# DP_eDP_Adapter_v1_1.net
KiCad netlist of a schematic drawn in EAGLE
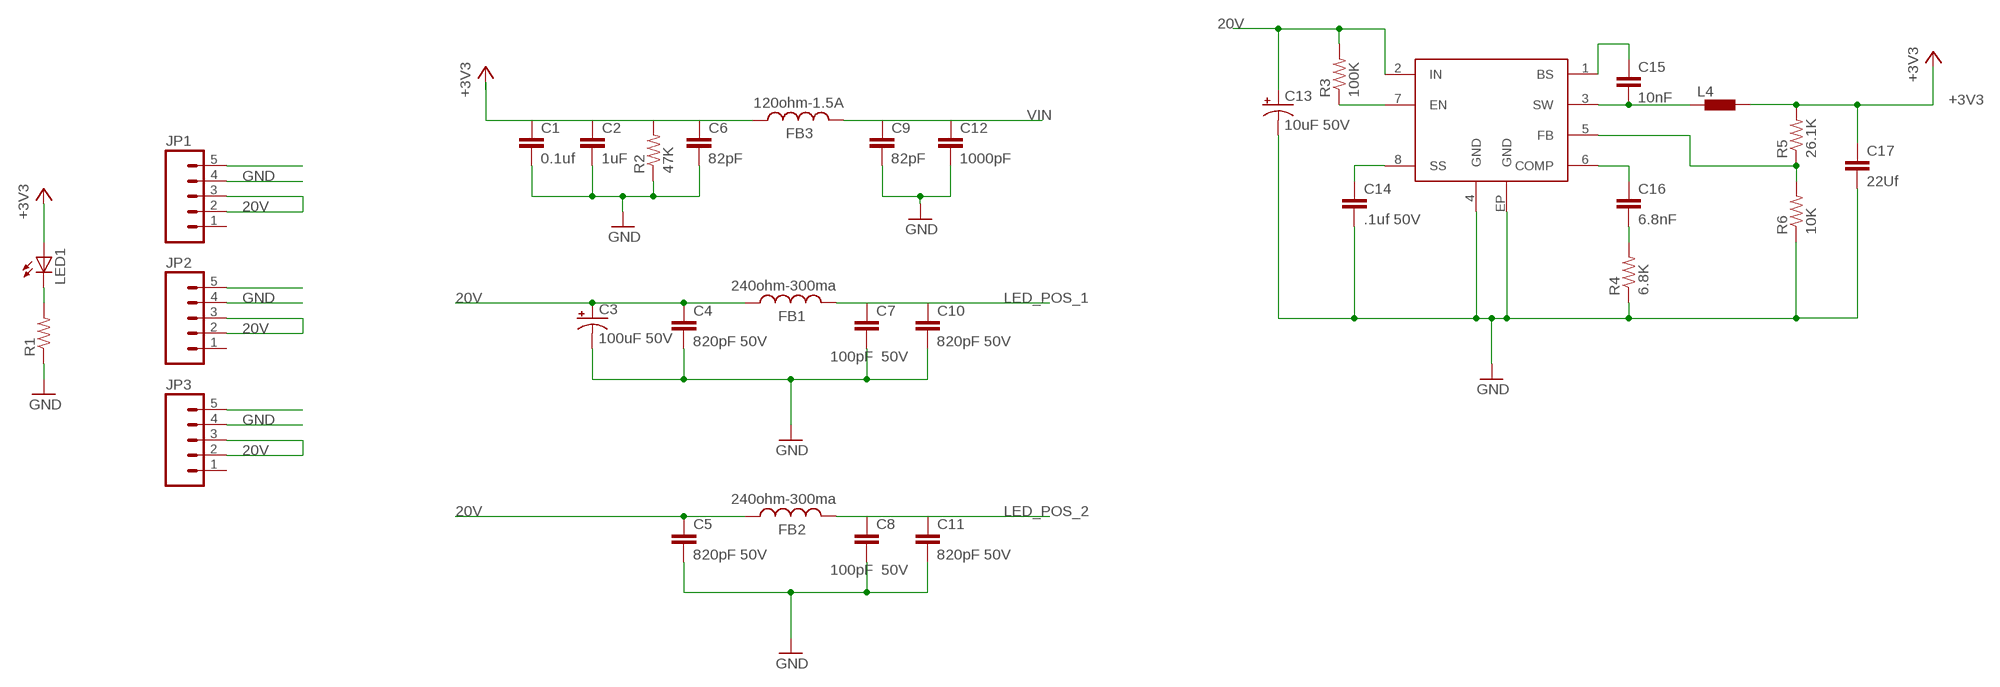
[diagram p0: schematic, sheet 1]
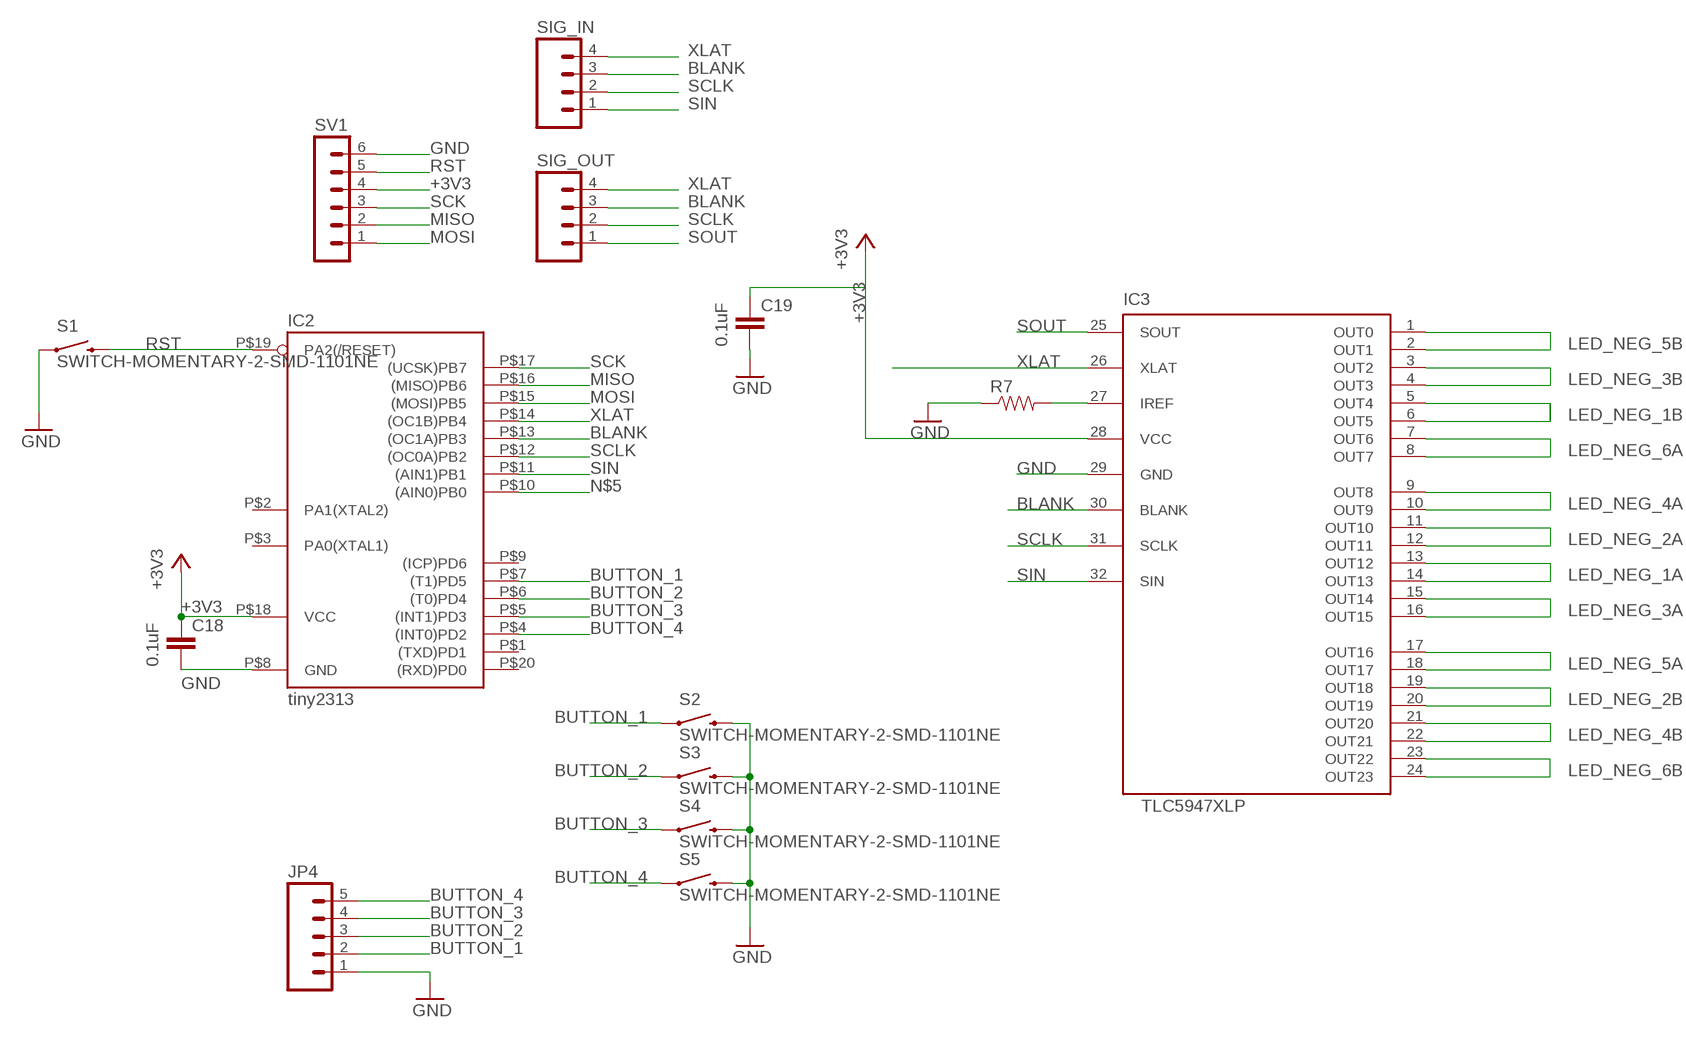
[diagram p1: schematic, sheet 2]
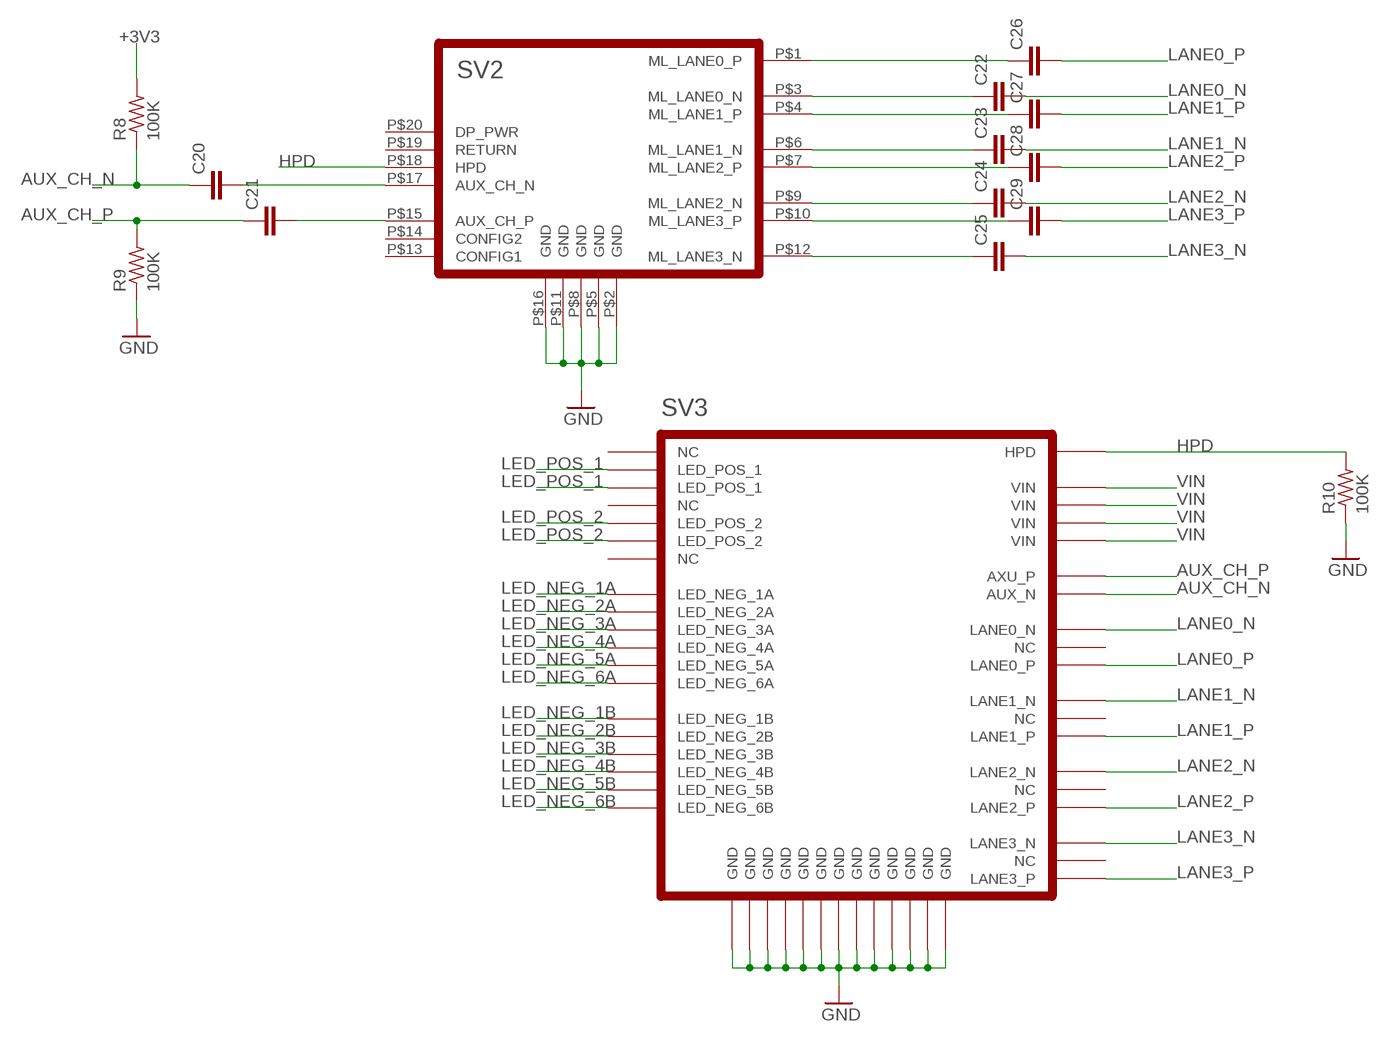
[diagram p2: schematic, sheet 3]

(export (version "E")
  (design (tool "Eeschema 10.0.6"))
  (components
    (comp (ref "C20")
      (value "SPARKFUN-PASSIVES_CAP0402-CAP")
      (footprint "eagle-import:SPARKFUN-PASSIVES_0402-CAP")
      (libsource (lib "eagle-import") (part "SPARKFUN-PASSIVES_CAP0402-CAP"))
    )
    (comp (ref "C21")
      (value "SPARKFUN-PASSIVES_CAP0402-CAP")
      (footprint "eagle-import:SPARKFUN-PASSIVES_0402-CAP")
      (libsource (lib "eagle-import") (part "SPARKFUN-PASSIVES_CAP0402-CAP"))
    )
    (comp (ref "C22")
      (value "SPARKFUN-PASSIVES_CAP0402-CAP")
      (footprint "eagle-import:SPARKFUN-PASSIVES_0402-CAP")
      (libsource (lib "eagle-import") (part "SPARKFUN-PASSIVES_CAP0402-CAP"))
    )
    (comp (ref "C23")
      (value "SPARKFUN-PASSIVES_CAP0402-CAP")
      (footprint "eagle-import:SPARKFUN-PASSIVES_0402-CAP")
      (libsource (lib "eagle-import") (part "SPARKFUN-PASSIVES_CAP0402-CAP"))
    )
    (comp (ref "C24")
      (value "SPARKFUN-PASSIVES_CAP0402-CAP")
      (footprint "eagle-import:SPARKFUN-PASSIVES_0402-CAP")
      (libsource (lib "eagle-import") (part "SPARKFUN-PASSIVES_CAP0402-CAP"))
    )
    (comp (ref "C25")
      (value "SPARKFUN-PASSIVES_CAP0402-CAP")
      (footprint "eagle-import:SPARKFUN-PASSIVES_0402-CAP")
      (libsource (lib "eagle-import") (part "SPARKFUN-PASSIVES_CAP0402-CAP"))
    )
    (comp (ref "C26")
      (value "SPARKFUN-PASSIVES_CAP0402-CAP")
      (footprint "eagle-import:SPARKFUN-PASSIVES_0402-CAP")
      (libsource (lib "eagle-import") (part "SPARKFUN-PASSIVES_CAP0402-CAP"))
    )
    (comp (ref "C27")
      (value "SPARKFUN-PASSIVES_CAP0402-CAP")
      (footprint "eagle-import:SPARKFUN-PASSIVES_0402-CAP")
      (libsource (lib "eagle-import") (part "SPARKFUN-PASSIVES_CAP0402-CAP"))
    )
    (comp (ref "C28")
      (value "SPARKFUN-PASSIVES_CAP0402-CAP")
      (footprint "eagle-import:SPARKFUN-PASSIVES_0402-CAP")
      (libsource (lib "eagle-import") (part "SPARKFUN-PASSIVES_CAP0402-CAP"))
    )
    (comp (ref "C29")
      (value "SPARKFUN-PASSIVES_CAP0402-CAP")
      (footprint "eagle-import:SPARKFUN-PASSIVES_0402-CAP")
      (libsource (lib "eagle-import") (part "SPARKFUN-PASSIVES_CAP0402-CAP"))
    )
    (comp (ref "R8")
      (value "100K")
      (footprint "eagle-import:R0402")
      (libsource (lib "eagle-import") (part "R-US_R0402"))
    )
    (comp (ref "R9")
      (value "100K")
      (footprint "eagle-import:R0402")
      (libsource (lib "eagle-import") (part "R-US_R0402"))
    )
    (comp (ref "R10")
      (value "100K")
      (footprint "eagle-import:R0402")
      (libsource (lib "eagle-import") (part "R-US_R0402"))
    )
    (comp (ref "SV2")
      (value "DP1RD20JQ2R400")
      (footprint "eagle-import:DP_REVERSE_JAE")
      (libsource (lib "eagle-import") (part "DP1RD20JQ2R400"))
    )
    (comp (ref "SV3")
      (value "DP_EDP_ADAPTER_EDP_CONNECTOR")
      (footprint "eagle-import:DP_EDP_ADAPTER_EDP_MOLEX")
      (libsource (lib "eagle-import") (part "DP_EDP_ADAPTER_EDP_CONNECTOR"))
    )
    (comp (ref "C1")
      (value "0.1uf")
      (footprint "eagle-import:0402-CAP")
      (libsource (lib "eagle-import") (part "SparkFun-Passives_CAP0402-CAP"))
    )
    (comp (ref "C2")
      (value "1uF")
      (footprint "eagle-import:0402-CAP")
      (libsource (lib "eagle-import") (part "SparkFun-Passives_CAP0402-CAP"))
    )
    (comp (ref "C3")
      (value "100uF 50V")
      (footprint "eagle-import:EIA6032")
      (libsource (lib "eagle-import") (part "CAP_POL6032"))
    )
    (comp (ref "C4")
      (value "820pF 50V")
      (footprint "eagle-import:0402-CAP")
      (libsource (lib "eagle-import") (part "SparkFun-Passives_CAP0402-CAP"))
    )
    (comp (ref "C5")
      (value "820pF 50V")
      (footprint "eagle-import:0402-CAP")
      (libsource (lib "eagle-import") (part "SparkFun-Passives_CAP0402-CAP"))
    )
    (comp (ref "C6")
      (value "82pF")
      (footprint "eagle-import:0402-CAP")
      (libsource (lib "eagle-import") (part "SparkFun-Passives_CAP0402-CAP"))
    )
    (comp (ref "C7")
      (value "100pF 50V")
      (footprint "eagle-import:0402-CAP")
      (libsource (lib "eagle-import") (part "SparkFun-Passives_CAP0402-CAP"))
    )
    (comp (ref "C8")
      (value "100pF 50V")
      (footprint "eagle-import:0402-CAP")
      (libsource (lib "eagle-import") (part "SparkFun-Passives_CAP0402-CAP"))
    )
    (comp (ref "C9")
      (value "82pF")
      (footprint "eagle-import:0402-CAP")
      (libsource (lib "eagle-import") (part "SparkFun-Passives_CAP0402-CAP"))
    )
    (comp (ref "C10")
      (value "820pF 50V")
      (footprint "eagle-import:0402-CAP")
      (libsource (lib "eagle-import") (part "SparkFun-Passives_CAP0402-CAP"))
    )
    (comp (ref "C11")
      (value "820pF 50V")
      (footprint "eagle-import:0402-CAP")
      (libsource (lib "eagle-import") (part "SparkFun-Passives_CAP0402-CAP"))
    )
    (comp (ref "C12")
      (value "1000pF")
      (footprint "eagle-import:0402-CAP")
      (libsource (lib "eagle-import") (part "SparkFun-Passives_CAP0402-CAP"))
    )
    (comp (ref "C13")
      (value "10uF 50V")
      (footprint "eagle-import:EIA6032")
      (libsource (lib "eagle-import") (part "CAP_POL6032"))
    )
    (comp (ref "C14")
      (value ".1uf 50V")
      (footprint "eagle-import:0402-CAP")
      (libsource (lib "eagle-import") (part "SparkFun-Passives_CAP0402-CAP"))
    )
    (comp (ref "C15")
      (value "10nF")
      (footprint "eagle-import:1206")
      (libsource (lib "eagle-import") (part "SparkFun-Passives_CAP1206"))
    )
    (comp (ref "C16")
      (value "6.8nF")
      (footprint "eagle-import:0402-CAP")
      (libsource (lib "eagle-import") (part "SparkFun-Passives_CAP0402-CAP"))
    )
    (comp (ref "C17")
      (value "22Uf")
      (footprint "eagle-import:0402-CAP")
      (libsource (lib "eagle-import") (part "SparkFun-Passives_CAP0402-CAP"))
    )
    (comp (ref "FB1")
      (value "240ohm-300ma")
      (footprint "eagle-import:R0402")
      (libsource (lib "eagle-import") (part "L-US"))
    )
    (comp (ref "FB2")
      (value "240ohm-300ma")
      (footprint "eagle-import:R0402")
      (libsource (lib "eagle-import") (part "L-US"))
    )
    (comp (ref "FB3")
      (value "120ohm-1.5A")
      (footprint "eagle-import:R0402")
      (libsource (lib "eagle-import") (part "L-US"))
    )
    (comp (ref "IC1")
      (value "AP6502A")
      (footprint "eagle-import:SO8-EP")
      (libsource (lib "eagle-import") (part "AP6502A"))
    )
    (comp (ref "JP1")
      (value "M05PTH")
      (footprint "eagle-import:1X05")
      (libsource (lib "eagle-import") (part "M05PTH"))
    )
    (comp (ref "JP2")
      (value "M05PTH")
      (footprint "eagle-import:1X05")
      (libsource (lib "eagle-import") (part "M05PTH"))
    )
    (comp (ref "JP3")
      (value "M05PTH")
      (footprint "eagle-import:1X05")
      (libsource (lib "eagle-import") (part "M05PTH"))
    )
    (comp (ref "L4")
      (value "INDUCTORS_DR10300520C")
      (footprint "eagle-import:0520C")
      (libsource (lib "eagle-import") (part "INDUCTORS_DR10300520C"))
    )
    (comp (ref "LED1")
      (value "LED_LEDCHIPLED_1206")
      (footprint "eagle-import:LED_CHIPLED_1206")
      (libsource (lib "eagle-import") (part "LED_LEDCHIPLED_1206"))
    )
    (comp (ref "R1")
      (value "RESISTOR0402-RES")
      (footprint "eagle-import:0402-RES")
      (libsource (lib "eagle-import") (part "RESISTOR0402-RES"))
    )
    (comp (ref "R2")
      (value "47K")
      (footprint "eagle-import:0402-RES")
      (libsource (lib "eagle-import") (part "RESISTOR0402-RES"))
    )
    (comp (ref "R3")
      (value "100K")
      (footprint "eagle-import:0402-RES")
      (libsource (lib "eagle-import") (part "RESISTOR0402-RES"))
    )
    (comp (ref "R4")
      (value "6.8K")
      (footprint "eagle-import:0402-RES")
      (libsource (lib "eagle-import") (part "RESISTOR0402-RES"))
    )
    (comp (ref "R5")
      (value "26.1K")
      (footprint "eagle-import:0402-RES")
      (libsource (lib "eagle-import") (part "RESISTOR0402-RES"))
    )
    (comp (ref "R6")
      (value "10K")
      (footprint "eagle-import:0402-RES")
      (libsource (lib "eagle-import") (part "RESISTOR0402-RES"))
    )
    (comp (ref "C18")
      (value "0.1uF")
      (footprint "eagle-import:0402-CAP")
      (libsource (lib "eagle-import") (part "CAP0402-CAP"))
    )
    (comp (ref "C19")
      (value "0.1uF")
      (footprint "eagle-import:0402-CAP")
      (libsource (lib "eagle-import") (part "CAP0402-CAP"))
    )
    (comp (ref "IC2")
      (value "tiny2313")
      (footprint "eagle-import:MLF20")
      (libsource (lib "eagle-import") (part "TINY2313-M"))
    )
    (comp (ref "IC3")
      (value "TLC5947XLP")
      (footprint "eagle-import:QFN32_XLP")
      (libsource (lib "eagle-import") (part "TLC5947XLP"))
    )
    (comp (ref "JP4")
      (value "M05PTH")
      (footprint "eagle-import:1X05")
      (libsource (lib "eagle-import") (part "M05PTH"))
    )
    (comp (ref "R7")
      (value "RESISTOR0402-RES")
      (footprint "eagle-import:0402-RES")
      (libsource (lib "eagle-import") (part "RESISTOR0402-RES"))
    )
    (comp (ref "S1")
      (value "SWITCH-MOMENTARY-2-SMD-1101NE")
      (footprint "eagle-import:TACTILE-SWITCH-1101NE")
      (libsource (lib "eagle-import") (part "SWITCH-MOMENTARY-2-SMD-1101NE"))
    )
    (comp (ref "S2")
      (value "SWITCH-MOMENTARY-2-SMD-1101NE")
      (footprint "eagle-import:TACTILE-SWITCH-1101NE")
      (libsource (lib "eagle-import") (part "SWITCH-MOMENTARY-2-SMD-1101NE"))
    )
    (comp (ref "S3")
      (value "SWITCH-MOMENTARY-2-SMD-1101NE")
      (footprint "eagle-import:TACTILE-SWITCH-1101NE")
      (libsource (lib "eagle-import") (part "SWITCH-MOMENTARY-2-SMD-1101NE"))
    )
    (comp (ref "S4")
      (value "SWITCH-MOMENTARY-2-SMD-1101NE")
      (footprint "eagle-import:TACTILE-SWITCH-1101NE")
      (libsource (lib "eagle-import") (part "SWITCH-MOMENTARY-2-SMD-1101NE"))
    )
    (comp (ref "S5")
      (value "SWITCH-MOMENTARY-2-SMD-1101NE")
      (footprint "eagle-import:TACTILE-SWITCH-1101NE")
      (libsource (lib "eagle-import") (part "SWITCH-MOMENTARY-2-SMD-1101NE"))
    )
    (comp (ref "SIG_IN")
      (value "M04PTH")
      (footprint "eagle-import:1X04")
      (libsource (lib "eagle-import") (part "M04PTH"))
    )
    (comp (ref "SIG_OUT")
      (value "M04PTH")
      (footprint "eagle-import:1X04")
      (libsource (lib "eagle-import") (part "M04PTH"))
    )
    (comp (ref "SV1")
      (value "MA06-1")
      (footprint "eagle-import:MA06-1")
      (libsource (lib "eagle-import") (part "MA06-1"))
    )
  )
  (nets
    (net (code "1") (name "+3V3") (class "Default")
      (node (ref "C1") (pin "1") (pinfunction "1_1") (pintype "passive"))
      (node (ref "C17") (pin "1") (pinfunction "1_1") (pintype "passive"))
      (node (ref "C18") (pin "1") (pinfunction "1_1") (pintype "passive"))
      (node (ref "C19") (pin "1") (pinfunction "1_1") (pintype "passive"))
      (node (ref "C2") (pin "1") (pinfunction "1_1") (pintype "passive"))
      (node (ref "C6") (pin "1") (pinfunction "1_1") (pintype "passive"))
      (node (ref "FB3") (pin "1") (pinfunction "1_1") (pintype "passive"))
      (node (ref "IC2") (pin "P$18") (pinfunction "VCC_P$18") (pintype "power_in"))
      (node (ref "IC3") (pin "28") (pinfunction "VCC_28") (pintype "bidirectional"))
      (node (ref "L4") (pin "P$2") (pinfunction "2_P$2") (pintype "passive"))
      (node (ref "LED1") (pin "A") (pinfunction "A_A") (pintype "passive"))
      (node (ref "R2") (pin "2") (pinfunction "2_2") (pintype "passive"))
      (node (ref "R5") (pin "2") (pinfunction "2_2") (pintype "passive"))
      (node (ref "R8") (pin "2") (pinfunction "2_2") (pintype "passive"))
      (node (ref "SV1") (pin "4") (pinfunction "4_4") (pintype "passive"))
    )
    (net (code "2") (name "20V") (class "Default")
      (node (ref "C13") (pin "P$1") (pinfunction "+_P$1") (pintype "passive"))
      (node (ref "C3") (pin "P$1") (pinfunction "+_P$1") (pintype "passive"))
      (node (ref "C4") (pin "1") (pinfunction "1_1") (pintype "passive"))
      (node (ref "C5") (pin "1") (pinfunction "1_1") (pintype "passive"))
      (node (ref "FB1") (pin "1") (pinfunction "1_1") (pintype "passive"))
      (node (ref "FB2") (pin "1") (pinfunction "1_1") (pintype "passive"))
      (node (ref "IC1") (pin "2") (pinfunction "IN_2") (pintype "bidirectional"))
      (node (ref "JP1") (pin "2") (pinfunction "2_2") (pintype "passive"))
      (node (ref "JP1") (pin "3") (pinfunction "3_3") (pintype "passive"))
      (node (ref "JP2") (pin "2") (pinfunction "2_2") (pintype "passive"))
      (node (ref "JP2") (pin "3") (pinfunction "3_3") (pintype "passive"))
      (node (ref "JP3") (pin "2") (pinfunction "2_2") (pintype "passive"))
      (node (ref "JP3") (pin "3") (pinfunction "3_3") (pintype "passive"))
      (node (ref "R3") (pin "2") (pinfunction "2_2") (pintype "passive"))
    )
    (net (code "3") (name "AUX_CH_N") (class "Default")
      (node (ref "C20") (pin "1") (pinfunction "1_1") (pintype "passive"))
      (node (ref "R8") (pin "1") (pinfunction "1_1") (pintype "passive"))
      (node (ref "SV3") (pin "P$10") (pinfunction "AUX_N_P$10") (pintype "bidirectional"))
    )
    (net (code "4") (name "AUX_CH_P") (class "Default")
      (node (ref "C21") (pin "1") (pinfunction "1_1") (pintype "passive"))
      (node (ref "R9") (pin "2") (pinfunction "2_2") (pintype "passive"))
      (node (ref "SV3") (pin "P$9") (pinfunction "AXU_P_P$9") (pintype "bidirectional"))
    )
    (net (code "5") (name "BLANK") (class "Default")
      (node (ref "IC2") (pin "P$13") (pinfunction "(OC1A)PB3_P$13") (pintype "bidirectional"))
      (node (ref "IC3") (pin "30") (pinfunction "BLANK_30") (pintype "bidirectional"))
      (node (ref "SIG_IN") (pin "3") (pinfunction "3_3") (pintype "passive"))
      (node (ref "SIG_OUT") (pin "3") (pinfunction "3_3") (pintype "passive"))
    )
    (net (code "6") (name "BUTTON_1") (class "Default")
      (node (ref "IC2") (pin "P$7") (pinfunction "(T1)PD5_P$7") (pintype "bidirectional"))
      (node (ref "JP4") (pin "2") (pinfunction "2_2") (pintype "passive"))
      (node (ref "S2") (pin "P$1") (pinfunction "1_P$1") (pintype "passive"))
    )
    (net (code "7") (name "BUTTON_2") (class "Default")
      (node (ref "IC2") (pin "P$6") (pinfunction "(T0)PD4_P$6") (pintype "bidirectional"))
      (node (ref "JP4") (pin "3") (pinfunction "3_3") (pintype "passive"))
      (node (ref "S3") (pin "P$1") (pinfunction "1_P$1") (pintype "passive"))
    )
    (net (code "8") (name "BUTTON_3") (class "Default")
      (node (ref "IC2") (pin "P$5") (pinfunction "(INT1)PD3_P$5") (pintype "bidirectional"))
      (node (ref "JP4") (pin "4") (pinfunction "4_4") (pintype "passive"))
      (node (ref "S4") (pin "P$1") (pinfunction "1_P$1") (pintype "passive"))
    )
    (net (code "9") (name "BUTTON_4") (class "Default")
      (node (ref "IC2") (pin "P$4") (pinfunction "(INT0)PD2_P$4") (pintype "bidirectional"))
      (node (ref "JP4") (pin "5") (pinfunction "5_5") (pintype "passive"))
      (node (ref "S5") (pin "P$1") (pinfunction "1_P$1") (pintype "passive"))
    )
    (net (code "10") (name "GND") (class "Default")
      (node (ref "C1") (pin "2") (pinfunction "2_2") (pintype "passive"))
      (node (ref "C10") (pin "2") (pinfunction "2_2") (pintype "passive"))
      (node (ref "C11") (pin "2") (pinfunction "2_2") (pintype "passive"))
      (node (ref "C12") (pin "2") (pinfunction "2_2") (pintype "passive"))
      (node (ref "C13") (pin "P$2") (pinfunction "-_P$2") (pintype "passive"))
      (node (ref "C14") (pin "2") (pinfunction "2_2") (pintype "passive"))
      (node (ref "C17") (pin "2") (pinfunction "2_2") (pintype "passive"))
      (node (ref "C18") (pin "2") (pinfunction "2_2") (pintype "passive"))
      (node (ref "C19") (pin "2") (pinfunction "2_2") (pintype "passive"))
      (node (ref "C2") (pin "2") (pinfunction "2_2") (pintype "passive"))
      (node (ref "C3") (pin "P$2") (pinfunction "-_P$2") (pintype "passive"))
      (node (ref "C4") (pin "2") (pinfunction "2_2") (pintype "passive"))
      (node (ref "C5") (pin "2") (pinfunction "2_2") (pintype "passive"))
      (node (ref "C6") (pin "2") (pinfunction "2_2") (pintype "passive"))
      (node (ref "C7") (pin "2") (pinfunction "2_2") (pintype "passive"))
      (node (ref "C8") (pin "2") (pinfunction "2_2") (pintype "passive"))
      (node (ref "C9") (pin "2") (pinfunction "2_2") (pintype "passive"))
      (node (ref "IC1") (pin "4") (pinfunction "GND_4") (pintype "bidirectional"))
      (node (ref "IC1") (pin "EP") (pinfunction "GND_EP") (pintype "bidirectional"))
      (node (ref "IC2") (pin "P$8") (pinfunction "GND_P$8") (pintype "power_in"))
      (node (ref "IC3") (pin "29") (pinfunction "GND_29") (pintype "bidirectional"))
      (node (ref "JP1") (pin "4") (pinfunction "4_4") (pintype "passive"))
      (node (ref "JP1") (pin "5") (pinfunction "5_5") (pintype "passive"))
      (node (ref "JP2") (pin "4") (pinfunction "4_4") (pintype "passive"))
      (node (ref "JP2") (pin "5") (pinfunction "5_5") (pintype "passive"))
      (node (ref "JP3") (pin "4") (pinfunction "4_4") (pintype "passive"))
      (node (ref "JP3") (pin "5") (pinfunction "5_5") (pintype "passive"))
      (node (ref "JP4") (pin "1") (pinfunction "1_1") (pintype "passive"))
      (node (ref "R1") (pin "1") (pinfunction "1_1") (pintype "passive"))
      (node (ref "R10") (pin "1") (pinfunction "1_1") (pintype "passive"))
      (node (ref "R2") (pin "1") (pinfunction "1_1") (pintype "passive"))
      (node (ref "R4") (pin "1") (pinfunction "1_1") (pintype "passive"))
      (node (ref "R6") (pin "1") (pinfunction "1_1") (pintype "passive"))
      (node (ref "R7") (pin "1") (pinfunction "1_1") (pintype "passive"))
      (node (ref "R9") (pin "1") (pinfunction "1_1") (pintype "passive"))
      (node (ref "S1") (pin "P$1") (pinfunction "1_P$1") (pintype "passive"))
      (node (ref "S2") (pin "P$2") (pinfunction "2_P$2") (pintype "passive"))
      (node (ref "S3") (pin "P$2") (pinfunction "2_P$2") (pintype "passive"))
      (node (ref "S4") (pin "P$2") (pinfunction "2_P$2") (pintype "passive"))
      (node (ref "S5") (pin "P$2") (pinfunction "2_P$2") (pintype "passive"))
      (node (ref "SV1") (pin "6") (pinfunction "6_6") (pintype "passive"))
      (node (ref "SV2") (pin "P$11") (pinfunction "GND_P$11") (pintype "bidirectional"))
      (node (ref "SV2") (pin "P$16") (pinfunction "GND_P$16") (pintype "bidirectional"))
      (node (ref "SV2") (pin "P$2") (pinfunction "GND_P$2") (pintype "bidirectional"))
      (node (ref "SV2") (pin "P$5") (pinfunction "GND_P$5") (pintype "bidirectional"))
      (node (ref "SV2") (pin "P$8") (pinfunction "GND_P$8") (pintype "bidirectional"))
      (node (ref "SV3") (pin "P$1") (pinfunction "GND_P$1") (pintype "bidirectional"))
      (node (ref "SV3") (pin "P$11") (pinfunction "GND_P$11") (pintype "bidirectional"))
      (node (ref "SV3") (pin "P$15") (pinfunction "GND_P$15") (pintype "bidirectional"))
      (node (ref "SV3") (pin "P$19") (pinfunction "GND_P$19") (pintype "bidirectional"))
      (node (ref "SV3") (pin "P$23") (pinfunction "GND_P$23") (pintype "bidirectional"))
      (node (ref "SV3") (pin "P$27") (pinfunction "GND_P$27") (pintype "bidirectional"))
      (node (ref "SV3") (pin "P$28") (pinfunction "GND_P$28") (pintype "bidirectional"))
      (node (ref "SV3") (pin "P$29") (pinfunction "GND_P$29") (pintype "bidirectional"))
      (node (ref "SV3") (pin "P$3") (pinfunction "GND_P$3") (pintype "bidirectional"))
      (node (ref "SV3") (pin "P$36") (pinfunction "GND_P$36") (pintype "bidirectional"))
      (node (ref "SV3") (pin "P$43") (pinfunction "GND_P$43") (pintype "bidirectional"))
      (node (ref "SV3") (pin "P$51") (pinfunction "GND_P$51") (pintype "bidirectional"))
      (node (ref "SV3") (pin "P$8") (pinfunction "GND_P$8") (pintype "bidirectional"))
    )
    (net (code "11") (name "HPD") (class "Default")
      (node (ref "R10") (pin "2") (pinfunction "2_2") (pintype "passive"))
      (node (ref "SV2") (pin "P$18") (pinfunction "HPD_P$18") (pintype "bidirectional"))
      (node (ref "SV3") (pin "P$2") (pinfunction "HPD_P$2") (pintype "bidirectional"))
    )
    (net (code "12") (name "LANE0_N") (class "Default")
      (node (ref "C22") (pin "2") (pinfunction "2_2") (pintype "passive"))
      (node (ref "SV3") (pin "P$12") (pinfunction "LANE0_N_P$12") (pintype "bidirectional"))
    )
    (net (code "13") (name "LANE0_P") (class "Default")
      (node (ref "C26") (pin "2") (pinfunction "2_2") (pintype "passive"))
      (node (ref "SV3") (pin "P$14") (pinfunction "LANE0_P_P$14") (pintype "bidirectional"))
    )
    (net (code "14") (name "LANE1_N") (class "Default")
      (node (ref "C23") (pin "2") (pinfunction "2_2") (pintype "passive"))
      (node (ref "SV3") (pin "P$16") (pinfunction "LANE1_N_P$16") (pintype "bidirectional"))
    )
    (net (code "15") (name "LANE1_P") (class "Default")
      (node (ref "C27") (pin "2") (pinfunction "2_2") (pintype "passive"))
      (node (ref "SV3") (pin "P$18") (pinfunction "LANE1_P_P$18") (pintype "bidirectional"))
    )
    (net (code "16") (name "LANE2_N") (class "Default")
      (node (ref "C24") (pin "2") (pinfunction "2_2") (pintype "passive"))
      (node (ref "SV3") (pin "P$20") (pinfunction "LANE2_N_P$20") (pintype "bidirectional"))
    )
    (net (code "17") (name "LANE2_P") (class "Default")
      (node (ref "C28") (pin "2") (pinfunction "2_2") (pintype "passive"))
      (node (ref "SV3") (pin "P$22") (pinfunction "LANE2_P_P$22") (pintype "bidirectional"))
    )
    (net (code "18") (name "LANE3_N") (class "Default")
      (node (ref "C25") (pin "2") (pinfunction "2_2") (pintype "passive"))
      (node (ref "SV3") (pin "P$24") (pinfunction "LANE3_N_P$24") (pintype "bidirectional"))
    )
    (net (code "19") (name "LANE3_P") (class "Default")
      (node (ref "C29") (pin "2") (pinfunction "2_2") (pintype "passive"))
      (node (ref "SV3") (pin "P$26") (pinfunction "LANE3_P_P$26") (pintype "bidirectional"))
    )
    (net (code "20") (name "LED_NEG_1A") (class "Default")
      (node (ref "IC3") (pin "13") (pinfunction "OUT12_13") (pintype "bidirectional"))
      (node (ref "IC3") (pin "14") (pinfunction "OUT13_14") (pintype "bidirectional"))
      (node (ref "SV3") (pin "P$42") (pinfunction "LED_NEG_1A_P$42") (pintype "bidirectional"))
    )
    (net (code "21") (name "LED_NEG_1B") (class "Default")
      (node (ref "IC3") (pin "5") (pinfunction "OUT4_5") (pintype "bidirectional"))
      (node (ref "IC3") (pin "6") (pinfunction "OUT5_6") (pintype "bidirectional"))
      (node (ref "SV3") (pin "P$35") (pinfunction "LED_NEG_1B_P$35") (pintype "bidirectional"))
    )
    (net (code "22") (name "LED_NEG_2A") (class "Default")
      (node (ref "IC3") (pin "11") (pinfunction "OUT10_11") (pintype "bidirectional"))
      (node (ref "IC3") (pin "12") (pinfunction "OUT11_12") (pintype "bidirectional"))
      (node (ref "SV3") (pin "P$41") (pinfunction "LED_NEG_2A_P$41") (pintype "bidirectional"))
    )
    (net (code "23") (name "LED_NEG_2B") (class "Default")
      (node (ref "IC3") (pin "19") (pinfunction "OUT18_19") (pintype "bidirectional"))
      (node (ref "IC3") (pin "20") (pinfunction "OUT19_20") (pintype "bidirectional"))
      (node (ref "SV3") (pin "P$34") (pinfunction "LED_NEG_2B_P$34") (pintype "bidirectional"))
    )
    (net (code "24") (name "LED_NEG_3A") (class "Default")
      (node (ref "IC3") (pin "15") (pinfunction "OUT14_15") (pintype "bidirectional"))
      (node (ref "IC3") (pin "16") (pinfunction "OUT15_16") (pintype "bidirectional"))
      (node (ref "SV3") (pin "P$40") (pinfunction "LED_NEG_3A_P$40") (pintype "bidirectional"))
    )
    (net (code "25") (name "LED_NEG_3B") (class "Default")
      (node (ref "IC3") (pin "3") (pinfunction "OUT2_3") (pintype "bidirectional"))
      (node (ref "IC3") (pin "4") (pinfunction "OUT3_4") (pintype "bidirectional"))
      (node (ref "SV3") (pin "P$33") (pinfunction "LED_NEG_3B_P$33") (pintype "bidirectional"))
    )
    (net (code "26") (name "LED_NEG_4A") (class "Default")
      (node (ref "IC3") (pin "10") (pinfunction "OUT9_10") (pintype "bidirectional"))
      (node (ref "IC3") (pin "9") (pinfunction "OUT8_9") (pintype "bidirectional"))
      (node (ref "SV3") (pin "P$39") (pinfunction "LED_NEG_4A_P$39") (pintype "bidirectional"))
    )
    (net (code "27") (name "LED_NEG_4B") (class "Default")
      (node (ref "IC3") (pin "21") (pinfunction "OUT20_21") (pintype "bidirectional"))
      (node (ref "IC3") (pin "22") (pinfunction "OUT21_22") (pintype "bidirectional"))
      (node (ref "SV3") (pin "P$32") (pinfunction "LED_NEG_4B_P$32") (pintype "bidirectional"))
    )
    (net (code "28") (name "LED_NEG_5A") (class "Default")
      (node (ref "IC3") (pin "17") (pinfunction "OUT16_17") (pintype "bidirectional"))
      (node (ref "IC3") (pin "18") (pinfunction "OUT17_18") (pintype "bidirectional"))
      (node (ref "SV3") (pin "P$38") (pinfunction "LED_NEG_5A_P$38") (pintype "bidirectional"))
    )
    (net (code "29") (name "LED_NEG_5B") (class "Default")
      (node (ref "IC3") (pin "1") (pinfunction "OUT0_1") (pintype "bidirectional"))
      (node (ref "IC3") (pin "2") (pinfunction "OUT1_2") (pintype "bidirectional"))
      (node (ref "SV3") (pin "P$31") (pinfunction "LED_NEG_5B_P$31") (pintype "bidirectional"))
    )
    (net (code "30") (name "LED_NEG_6A") (class "Default")
      (node (ref "IC3") (pin "7") (pinfunction "OUT6_7") (pintype "bidirectional"))
      (node (ref "IC3") (pin "8") (pinfunction "OUT7_8") (pintype "bidirectional"))
      (node (ref "SV3") (pin "P$37") (pinfunction "LED_NEG_6A_P$37") (pintype "bidirectional"))
    )
    (net (code "31") (name "LED_NEG_6B") (class "Default")
      (node (ref "IC3") (pin "23") (pinfunction "OUT22_23") (pintype "bidirectional"))
      (node (ref "IC3") (pin "24") (pinfunction "OUT23_24") (pintype "bidirectional"))
      (node (ref "SV3") (pin "P$30") (pinfunction "LED_NEG_6B_P$30") (pintype "bidirectional"))
    )
    (net (code "32") (name "LED_POS_1") (class "Default")
      (node (ref "C10") (pin "1") (pinfunction "1_1") (pintype "passive"))
      (node (ref "C7") (pin "1") (pinfunction "1_1") (pintype "passive"))
      (node (ref "FB1") (pin "2") (pinfunction "2_2") (pintype "passive"))
      (node (ref "SV3") (pin "P$48") (pinfunction "LED_POS_1_P$48") (pintype "bidirectional"))
      (node (ref "SV3") (pin "P$49") (pinfunction "LED_POS_1_P$49") (pintype "bidirectional"))
    )
    (net (code "33") (name "LED_POS_2") (class "Default")
      (node (ref "C11") (pin "1") (pinfunction "1_1") (pintype "passive"))
      (node (ref "C8") (pin "1") (pinfunction "1_1") (pintype "passive"))
      (node (ref "FB2") (pin "2") (pinfunction "2_2") (pintype "passive"))
      (node (ref "SV3") (pin "P$45") (pinfunction "LED_POS_2_P$45") (pintype "bidirectional"))
      (node (ref "SV3") (pin "P$46") (pinfunction "LED_POS_2_P$46") (pintype "bidirectional"))
    )
    (net (code "34") (name "MISO") (class "Default")
      (node (ref "IC2") (pin "P$16") (pinfunction "(MISO)PB6_P$16") (pintype "bidirectional"))
      (node (ref "SV1") (pin "2") (pinfunction "2_2") (pintype "passive"))
    )
    (net (code "35") (name "MOSI") (class "Default")
      (node (ref "IC2") (pin "P$15") (pinfunction "(MOSI)PB5_P$15") (pintype "bidirectional"))
      (node (ref "SV1") (pin "1") (pinfunction "1_1") (pintype "passive"))
    )
    (net (code "36") (name "N$5") (class "Default")
      (node (ref "IC2") (pin "P$10") (pinfunction "(AIN0)PB0_P$10") (pintype "bidirectional"))
    )
    (net (code "37") (name "Net-(C16-Pad2)") (class "Default")
      (node (ref "C16") (pin "2") (pinfunction "2_2") (pintype "passive"))
      (node (ref "R4") (pin "2") (pinfunction "2_2") (pintype "passive"))
    )
    (net (code "38") (name "Net-(IC1-BS)") (class "Default")
      (node (ref "C15") (pin "1") (pinfunction "1_1") (pintype "passive"))
      (node (ref "IC1") (pin "1") (pinfunction "BS_1") (pintype "bidirectional"))
    )
    (net (code "39") (name "Net-(IC1-COMP)") (class "Default")
      (node (ref "C16") (pin "1") (pinfunction "1_1") (pintype "passive"))
      (node (ref "IC1") (pin "6") (pinfunction "COMP_6") (pintype "bidirectional"))
    )
    (net (code "40") (name "Net-(IC1-EN)") (class "Default")
      (node (ref "IC1") (pin "7") (pinfunction "EN_7") (pintype "bidirectional"))
      (node (ref "R3") (pin "1") (pinfunction "1_1") (pintype "passive"))
    )
    (net (code "41") (name "Net-(IC1-FB)") (class "Default")
      (node (ref "IC1") (pin "5") (pinfunction "FB_5") (pintype "bidirectional"))
      (node (ref "R5") (pin "1") (pinfunction "1_1") (pintype "passive"))
      (node (ref "R6") (pin "2") (pinfunction "2_2") (pintype "passive"))
    )
    (net (code "42") (name "Net-(IC1-SS)") (class "Default")
      (node (ref "C14") (pin "1") (pinfunction "1_1") (pintype "passive"))
      (node (ref "IC1") (pin "8") (pinfunction "SS_8") (pintype "bidirectional"))
    )
    (net (code "43") (name "Net-(IC1-SW)") (class "Default")
      (node (ref "C15") (pin "2") (pinfunction "2_2") (pintype "passive"))
      (node (ref "IC1") (pin "3") (pinfunction "SW_3") (pintype "bidirectional"))
      (node (ref "L4") (pin "P$1") (pinfunction "1_P$1") (pintype "passive"))
    )
    (net (code "44") (name "Net-(IC3-IREF)") (class "Default")
      (node (ref "IC3") (pin "27") (pinfunction "IREF_27") (pintype "bidirectional"))
      (node (ref "R7") (pin "2") (pinfunction "2_2") (pintype "passive"))
    )
    (net (code "45") (name "Net-(LED1-PadC)") (class "Default")
      (node (ref "LED1") (pin "C") (pinfunction "C_C") (pintype "passive"))
      (node (ref "R1") (pin "2") (pinfunction "2_2") (pintype "passive"))
    )
    (net (code "46") (name "Net-(SV2-AUX_CH_N)") (class "Default")
      (node (ref "C20") (pin "2") (pinfunction "2_2") (pintype "passive"))
      (node (ref "SV2") (pin "P$17") (pinfunction "AUX_CH_N_P$17") (pintype "bidirectional"))
    )
    (net (code "47") (name "Net-(SV2-AUX_CH_P)") (class "Default")
      (node (ref "C21") (pin "2") (pinfunction "2_2") (pintype "passive"))
      (node (ref "SV2") (pin "P$15") (pinfunction "AUX_CH_P_P$15") (pintype "bidirectional"))
    )
    (net (code "48") (name "Net-(SV2-ML_LANE0_N)") (class "Default")
      (node (ref "C22") (pin "1") (pinfunction "1_1") (pintype "passive"))
      (node (ref "SV2") (pin "P$3") (pinfunction "ML_LANE0_N_P$3") (pintype "bidirectional"))
    )
    (net (code "49") (name "Net-(SV2-ML_LANE0_P)") (class "Default")
      (node (ref "C26") (pin "1") (pinfunction "1_1") (pintype "passive"))
      (node (ref "SV2") (pin "P$1") (pinfunction "ML_LANE0_P_P$1") (pintype "bidirectional"))
    )
    (net (code "50") (name "Net-(SV2-ML_LANE1_N)") (class "Default")
      (node (ref "C23") (pin "1") (pinfunction "1_1") (pintype "passive"))
      (node (ref "SV2") (pin "P$6") (pinfunction "ML_LANE1_N_P$6") (pintype "bidirectional"))
    )
    (net (code "51") (name "Net-(SV2-ML_LANE1_P)") (class "Default")
      (node (ref "C27") (pin "1") (pinfunction "1_1") (pintype "passive"))
      (node (ref "SV2") (pin "P$4") (pinfunction "ML_LANE1_P_P$4") (pintype "bidirectional"))
    )
    (net (code "52") (name "Net-(SV2-ML_LANE2_N)") (class "Default")
      (node (ref "C24") (pin "1") (pinfunction "1_1") (pintype "passive"))
      (node (ref "SV2") (pin "P$9") (pinfunction "ML_LANE2_N_P$9") (pintype "bidirectional"))
    )
    (net (code "53") (name "Net-(SV2-ML_LANE2_P)") (class "Default")
      (node (ref "C28") (pin "1") (pinfunction "1_1") (pintype "passive"))
      (node (ref "SV2") (pin "P$7") (pinfunction "ML_LANE2_P_P$7") (pintype "bidirectional"))
    )
    (net (code "54") (name "Net-(SV2-ML_LANE3_N)") (class "Default")
      (node (ref "C25") (pin "1") (pinfunction "1_1") (pintype "passive"))
      (node (ref "SV2") (pin "P$12") (pinfunction "ML_LANE3_N_P$12") (pintype "bidirectional"))
    )
    (net (code "55") (name "Net-(SV2-ML_LANE3_P)") (class "Default")
      (node (ref "C29") (pin "1") (pinfunction "1_1") (pintype "passive"))
      (node (ref "SV2") (pin "P$10") (pinfunction "ML_LANE3_P_P$10") (pintype "bidirectional"))
    )
    (net (code "56") (name "RST") (class "Default")
      (node (ref "IC2") (pin "P$19") (pinfunction "PA2(/RESET)_P$19") (pintype "input"))
      (node (ref "S1") (pin "P$2") (pinfunction "2_P$2") (pintype "passive"))
      (node (ref "SV1") (pin "5") (pinfunction "5_5") (pintype "passive"))
    )
    (net (code "57") (name "SCK") (class "Default")
      (node (ref "IC2") (pin "P$17") (pinfunction "(UCSK)PB7_P$17") (pintype "bidirectional"))
      (node (ref "SV1") (pin "3") (pinfunction "3_3") (pintype "passive"))
    )
    (net (code "58") (name "SCLK") (class "Default")
      (node (ref "IC2") (pin "P$12") (pinfunction "(OC0A)PB2_P$12") (pintype "bidirectional"))
      (node (ref "IC3") (pin "31") (pinfunction "SCLK_31") (pintype "bidirectional"))
      (node (ref "SIG_IN") (pin "2") (pinfunction "2_2") (pintype "passive"))
      (node (ref "SIG_OUT") (pin "2") (pinfunction "2_2") (pintype "passive"))
    )
    (net (code "59") (name "SIN") (class "Default")
      (node (ref "IC2") (pin "P$11") (pinfunction "(AIN1)PB1_P$11") (pintype "bidirectional"))
      (node (ref "IC3") (pin "32") (pinfunction "SIN_32") (pintype "bidirectional"))
      (node (ref "SIG_IN") (pin "1") (pinfunction "1_1") (pintype "passive"))
    )
    (net (code "60") (name "SOUT") (class "Default")
      (node (ref "IC3") (pin "25") (pinfunction "SOUT_25") (pintype "bidirectional"))
      (node (ref "SIG_OUT") (pin "1") (pinfunction "1_1") (pintype "passive"))
    )
    (net (code "61") (name "VIN") (class "Default")
      (node (ref "C12") (pin "1") (pinfunction "1_1") (pintype "passive"))
      (node (ref "C9") (pin "1") (pinfunction "1_1") (pintype "passive"))
      (node (ref "FB3") (pin "2") (pinfunction "2_2") (pintype "passive"))
      (node (ref "SV3") (pin "P$4") (pinfunction "VIN_P$4") (pintype "bidirectional"))
      (node (ref "SV3") (pin "P$5") (pinfunction "VIN_P$5") (pintype "bidirectional"))
      (node (ref "SV3") (pin "P$6") (pinfunction "VIN_P$6") (pintype "bidirectional"))
      (node (ref "SV3") (pin "P$7") (pinfunction "VIN_P$7") (pintype "bidirectional"))
    )
    (net (code "62") (name "XLAT") (class "Default")
      (node (ref "IC2") (pin "P$14") (pinfunction "(OC1B)PB4_P$14") (pintype "bidirectional"))
      (node (ref "IC3") (pin "26") (pinfunction "XLAT_26") (pintype "bidirectional"))
      (node (ref "SIG_IN") (pin "4") (pinfunction "4_4") (pintype "passive"))
      (node (ref "SIG_OUT") (pin "4") (pinfunction "4_4") (pintype "passive"))
    )
    (net (code "63") (name "unconnected-(IC2-(ICP)PD6-PadP$9)") (class "Default")
      (node (ref "IC2") (pin "P$9") (pinfunction "(ICP)PD6_P$9") (pintype "bidirectional"))
    )
    (net (code "64") (name "unconnected-(IC2-(RXD)PD0-PadP$20)") (class "Default")
      (node (ref "IC2") (pin "P$20") (pinfunction "(RXD)PD0_P$20") (pintype "bidirectional"))
    )
    (net (code "65") (name "unconnected-(IC2-(TXD)PD1-PadP$1)") (class "Default")
      (node (ref "IC2") (pin "P$1") (pinfunction "(TXD)PD1_P$1") (pintype "bidirectional"))
    )
    (net (code "66") (name "unconnected-(IC2-PA0(XTAL1)-PadP$3)") (class "Default")
      (node (ref "IC2") (pin "P$3") (pinfunction "PA0(XTAL1)_P$3") (pintype "bidirectional"))
    )
    (net (code "67") (name "unconnected-(IC2-PA1(XTAL2)-PadP$2)") (class "Default")
      (node (ref "IC2") (pin "P$2") (pinfunction "PA1(XTAL2)_P$2") (pintype "bidirectional"))
    )
    (net (code "68") (name "unconnected-(JP1-Pad1)") (class "Default")
      (node (ref "JP1") (pin "1") (pinfunction "1_1") (pintype "passive"))
    )
    (net (code "69") (name "unconnected-(JP2-Pad1)") (class "Default")
      (node (ref "JP2") (pin "1") (pinfunction "1_1") (pintype "passive"))
    )
    (net (code "70") (name "unconnected-(JP3-Pad1)") (class "Default")
      (node (ref "JP3") (pin "1") (pinfunction "1_1") (pintype "passive"))
    )
    (net (code "71") (name "unconnected-(SV2-CONFIG1-PadP$13)") (class "Default")
      (node (ref "SV2") (pin "P$13") (pinfunction "CONFIG1_P$13") (pintype "bidirectional"))
    )
    (net (code "72") (name "unconnected-(SV2-CONFIG2-PadP$14)") (class "Default")
      (node (ref "SV2") (pin "P$14") (pinfunction "CONFIG2_P$14") (pintype "bidirectional"))
    )
    (net (code "73") (name "unconnected-(SV2-DP_PWR-PadP$20)") (class "Default")
      (node (ref "SV2") (pin "P$20") (pinfunction "DP_PWR_P$20") (pintype "bidirectional"))
    )
    (net (code "74") (name "unconnected-(SV2-RETURN-PadP$19)") (class "Default")
      (node (ref "SV2") (pin "P$19") (pinfunction "RETURN_P$19") (pintype "bidirectional"))
    )
    (net (code "75") (name "unconnected-(SV3-NC-PadP$13)") (class "Default")
      (node (ref "SV3") (pin "P$13") (pinfunction "NC_P$13") (pintype "bidirectional"))
    )
    (net (code "76") (name "unconnected-(SV3-NC-PadP$17)") (class "Default")
      (node (ref "SV3") (pin "P$17") (pinfunction "NC_P$17") (pintype "bidirectional"))
    )
    (net (code "77") (name "unconnected-(SV3-NC-PadP$21)") (class "Default")
      (node (ref "SV3") (pin "P$21") (pinfunction "NC_P$21") (pintype "bidirectional"))
    )
    (net (code "78") (name "unconnected-(SV3-NC-PadP$25)") (class "Default")
      (node (ref "SV3") (pin "P$25") (pinfunction "NC_P$25") (pintype "bidirectional"))
    )
    (net (code "79") (name "unconnected-(SV3-NC-PadP$44)") (class "Default")
      (node (ref "SV3") (pin "P$44") (pinfunction "NC_P$44") (pintype "bidirectional"))
    )
    (net (code "80") (name "unconnected-(SV3-NC-PadP$47)") (class "Default")
      (node (ref "SV3") (pin "P$47") (pinfunction "NC_P$47") (pintype "bidirectional"))
    )
    (net (code "81") (name "unconnected-(SV3-NC-PadP$50)") (class "Default")
      (node (ref "SV3") (pin "P$50") (pinfunction "NC_P$50") (pintype "bidirectional"))
    )
  )
)
